# USB_Serial.net
KiCad netlist of a schematic drawn in Altium Designer
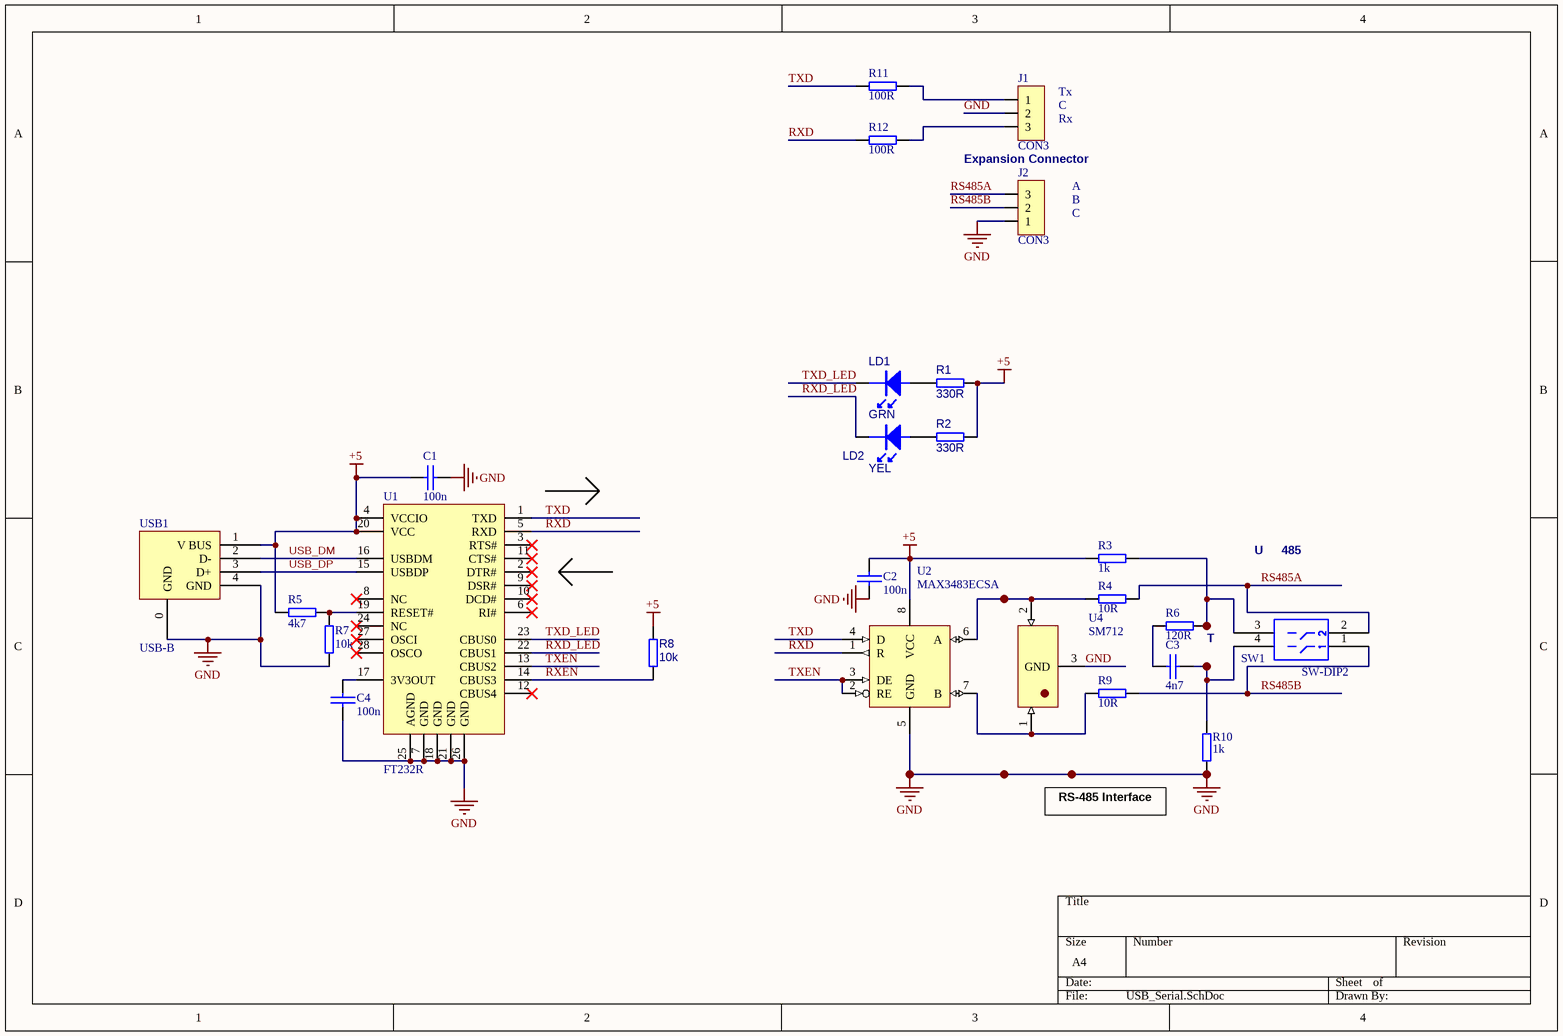
[diagram p0: USB_Serial.SchDoc]

(export (version "E")
  (design (tool "Eeschema 10.0.6"))
  (components
    (comp (ref "C1") (value "100n") (footprint "0603") (libsource (lib "*") (part "CAP")))
    (comp (ref "C2") (value "100n") (footprint "0603") (libsource (lib "*") (part "CAP")))
    (comp (ref "C3") (value "4n7") (footprint "0603") (libsource (lib "*") (part "CAP")))
    (comp (ref "C4") (value "100n") (footprint "0603") (libsource (lib "*") (part "CAP")))
    (comp (ref "J1") (value "CON3") (footprint "TERMS5mm3") (libsource (lib "") (part "CON3_1")))
    (comp (ref "J2") (value "CON3") (footprint "TERMS5mm3") (libsource (lib "DEVICE") (part "CON3")))
    (comp (ref "LD1") (value "GRN") (footprint "0805DIODE") (libsource (lib "*") (part "LED")))
    (comp (ref "LD2") (value "YEL") (footprint "0805DIODE") (libsource (lib "*") (part "LED")))
    (comp (ref "R1") (value "330R") (footprint "0603") (libsource (lib "DEVICE") (part "RES8")))
    (comp (ref "R2") (value "330R") (footprint "0603") (libsource (lib "DEVICE") (part "RES8")))
    (comp (ref "R3") (value "1k") (footprint "0603") (libsource (lib "*") (part "RES8")))
    (comp (ref "R4") (value "10R") (footprint "0603") (libsource (lib "*") (part "RES8")))
    (comp (ref "R5") (value "4k7") (footprint "0603") (libsource (lib "DEVICE") (part "RES8")))
    (comp (ref "R6") (value "120R") (footprint "0603") (libsource (lib "*") (part "RES8")))
    (comp (ref "R7") (value "10k") (footprint "0603") (libsource (lib "DEVICE") (part "RES8")))
    (comp (ref "R8") (value "10k") (footprint "0603") (libsource (lib "DEVICE") (part "RES8")))
    (comp (ref "R9") (value "10R") (footprint "0603") (libsource (lib "*") (part "RES8")))
    (comp (ref "R10") (value "1k") (footprint "0603") (libsource (lib "*") (part "RES8")))
    (comp (ref "R11") (value "100R") (footprint "0603") (libsource (lib "*") (part "RES8")))
    (comp (ref "R12") (value "100R") (footprint "0603") (libsource (lib "*") (part "RES8")))
    (comp (ref "SW1") (value "SW-DIP2") (footprint "DIP4") (libsource (lib "*") (part "SW-DIP2")))
    (comp (ref "U1")
      (value "FT232R")
      (footprint "SSOP28W-handsolder")
      (libsource (lib "FTDI") (part "FT232R"))
    )
    (comp (ref "U2")
      (value "MAX3483ECSA")
      (footprint "so-8")
      (description "RS485 Transceiver")
      (libsource (lib "*") (part "MAX487"))
    )
    (comp (ref "U4")
      (value "SM712")
      (footprint "sot-23")
      (description "RS485 Transorb")
      (fields (field (name "PARTNO.") "2059024"))
      (libsource (lib "TomsSchLib") (part "SM712"))
    )
    (comp (ref "USB1") (value "USB-B") (footprint "USB_MINI_B") (libsource (lib "DEVICE") (part "USB-B")))
  )
  (nets
    (net (code "1") (name "+5") (class "Default")
      (node (ref "C1") (pin "2") (pintype "passive"))
      (node (ref "C2") (pin "1") (pintype "passive"))
      (node (ref "R1") (pin "1") (pintype "passive"))
      (node (ref "R2") (pin "1") (pintype "passive"))
      (node (ref "R3") (pin "1") (pintype "passive"))
      (node (ref "R5") (pin "1") (pintype "passive"))
      (node (ref "R8") (pin "1") (pintype "passive"))
      (node (ref "U1") (pin "20") (pinfunction "VCC_20") (pintype "passive"))
      (node (ref "U1") (pin "4") (pinfunction "VCCIO_4") (pintype "passive"))
      (node (ref "U2") (pin "8") (pinfunction "VCC_8") (pintype "power_in"))
      (node (ref "USB1") (pin "1") (pinfunction "V_BUS_1") (pintype "passive"))
    )
    (net (code "2") (name "/RS485A") (class "Default")
      (node (ref "J2") (pin "3") (pinfunction "3_3") (pintype "passive"))
      (node (ref "R4") (pin "2") (pintype "passive"))
      (node (ref "SW1") (pin "2") (pintype "passive"))
    )
    (net (code "3") (name "/RS485B") (class "Default")
      (node (ref "J2") (pin "2") (pinfunction "2_2") (pintype "passive"))
      (node (ref "R9") (pin "2") (pintype "passive"))
      (node (ref "SW1") (pin "1") (pintype "passive"))
    )
    (net (code "4") (name "/RXD") (class "Default")
      (node (ref "R12") (pin "1") (pintype "passive"))
      (node (ref "U1") (pin "5") (pinfunction "RXD_5") (pintype "passive"))
      (node (ref "U2") (pin "1") (pinfunction "R_1") (pintype "output"))
    )
    (net (code "5") (name "/RXD_LED") (class "Default")
      (node (ref "LD2") (pin "K") (pintype "passive"))
      (node (ref "U1") (pin "22") (pinfunction "CBUS1_22") (pintype "passive"))
    )
    (net (code "6") (name "/RXEN") (class "Default")
      (node (ref "R8") (pin "2") (pintype "passive"))
      (node (ref "U1") (pin "14") (pinfunction "CBUS3_14") (pintype "passive"))
    )
    (net (code "7") (name "/TXD") (class "Default")
      (node (ref "R11") (pin "1") (pintype "passive"))
      (node (ref "U1") (pin "1") (pinfunction "TXD_1") (pintype "passive"))
      (node (ref "U2") (pin "4") (pinfunction "D_4") (pintype "input"))
    )
    (net (code "8") (name "/TXD_LED") (class "Default")
      (node (ref "LD1") (pin "K") (pintype "passive"))
      (node (ref "U1") (pin "23") (pinfunction "CBUS0_23") (pintype "passive"))
    )
    (net (code "9") (name "/TXEN") (class "Default")
      (node (ref "U1") (pin "13") (pinfunction "CBUS2_13") (pintype "passive"))
      (node (ref "U2") (pin "2") (pinfunction "RE_2") (pintype "input"))
      (node (ref "U2") (pin "3") (pinfunction "DE_3") (pintype "input"))
    )
    (net (code "10") (name "/USB_DM") (class "Default")
      (node (ref "U1") (pin "16") (pinfunction "USBDM_16") (pintype "passive"))
      (node (ref "USB1") (pin "2") (pinfunction "D-_2") (pintype "passive"))
    )
    (net (code "11") (name "/USB_DP") (class "Default")
      (node (ref "U1") (pin "15") (pinfunction "USBDP_15") (pintype "passive"))
      (node (ref "USB1") (pin "3") (pinfunction "D+_3") (pintype "passive"))
    )
    (net (code "12") (name "GND") (class "Default")
      (node (ref "C1") (pin "1") (pintype "passive"))
      (node (ref "C2") (pin "2") (pintype "passive"))
      (node (ref "C4") (pin "1") (pintype "passive"))
      (node (ref "J1") (pin "2") (pinfunction "2_2") (pintype "passive"))
      (node (ref "J2") (pin "1") (pinfunction "1_1") (pintype "passive"))
      (node (ref "R10") (pin "2") (pintype "passive"))
      (node (ref "R7") (pin "1") (pintype "passive"))
      (node (ref "U1") (pin "18") (pinfunction "GND_18") (pintype "passive"))
      (node (ref "U1") (pin "21") (pinfunction "GND_21") (pintype "passive"))
      (node (ref "U1") (pin "25") (pinfunction "AGND_25") (pintype "passive"))
      (node (ref "U1") (pin "26") (pinfunction "GND_26") (pintype "passive"))
      (node (ref "U1") (pin "7") (pinfunction "GND_7") (pintype "passive"))
      (node (ref "U2") (pin "5") (pinfunction "GND_5") (pintype "power_in"))
      (node (ref "U4") (pin "3") (pinfunction "GND_3") (pintype "power_in"))
      (node (ref "USB1") (pin "0") (pinfunction "GND_0") (pintype "power_in"))
      (node (ref "USB1") (pin "4") (pinfunction "GND_4") (pintype "passive"))
    )
    (net (code "13") (name "Net-(C3-Pad1)") (class "Default")
      (node (ref "C3") (pin "1") (pintype "passive"))
      (node (ref "R6") (pin "1") (pintype "passive"))
    )
    (net (code "14") (name "Net-(C3-Pad2)") (class "Default")
      (node (ref "C3") (pin "2") (pintype "passive"))
      (node (ref "R10") (pin "1") (pintype "passive"))
      (node (ref "SW1") (pin "4") (pintype "passive"))
    )
    (net (code "15") (name "Net-(J1-Pad1)") (class "Default")
      (node (ref "J1") (pin "1") (pinfunction "1_1") (pintype "passive"))
      (node (ref "R11") (pin "2") (pintype "passive"))
    )
    (net (code "16") (name "Net-(J1-Pad3)") (class "Default")
      (node (ref "J1") (pin "3") (pinfunction "3_3") (pintype "passive"))
      (node (ref "R12") (pin "2") (pintype "passive"))
    )
    (net (code "17") (name "Net-(LD1-PadA)") (class "Default")
      (node (ref "LD1") (pin "A") (pintype "passive"))
      (node (ref "R1") (pin "2") (pintype "passive"))
    )
    (net (code "18") (name "Net-(LD2-PadA)") (class "Default")
      (node (ref "LD2") (pin "A") (pintype "passive"))
      (node (ref "R2") (pin "2") (pintype "passive"))
    )
    (net (code "19") (name "Net-(R3-Pad2)") (class "Default")
      (node (ref "R3") (pin "2") (pintype "passive"))
      (node (ref "R6") (pin "2") (pintype "passive"))
      (node (ref "SW1") (pin "3") (pintype "passive"))
    )
    (net (code "20") (name "Net-(U1-3V3OUT)") (class "Default")
      (node (ref "C4") (pin "2") (pintype "passive"))
      (node (ref "U1") (pin "17") (pinfunction "3V3OUT_17") (pintype "passive"))
    )
    (net (code "21") (name "Net-(U1-RESET#)") (class "Default")
      (node (ref "R5") (pin "2") (pintype "passive"))
      (node (ref "R7") (pin "2") (pintype "passive"))
      (node (ref "U1") (pin "19") (pinfunction "RESET#_19") (pintype "passive"))
    )
    (net (code "22") (name "Net-(U2-A)") (class "Default")
      (node (ref "R4") (pin "1") (pintype "passive"))
      (node (ref "U2") (pin "6") (pinfunction "A_6") (pintype "bidirectional"))
      (node (ref "U4") (pin "2") (pintype "input"))
    )
    (net (code "23") (name "Net-(U2-B)") (class "Default")
      (node (ref "R9") (pin "1") (pintype "passive"))
      (node (ref "U2") (pin "7") (pinfunction "B_7") (pintype "bidirectional"))
      (node (ref "U4") (pin "1") (pintype "input"))
    )
    (net (code "24") (name "unconnected-(U1-CBUS4-Pad12)") (class "Default")
      (node (ref "U1") (pin "12") (pinfunction "CBUS4_12") (pintype "passive+no_connect"))
    )
    (net (code "25") (name "unconnected-(U1-CTS#-Pad11)") (class "Default")
      (node (ref "U1") (pin "11") (pinfunction "CTS#_11") (pintype "passive+no_connect"))
    )
    (net (code "26") (name "unconnected-(U1-DCD#-Pad10)") (class "Default")
      (node (ref "U1") (pin "10") (pinfunction "DCD#_10") (pintype "passive+no_connect"))
    )
    (net (code "27") (name "unconnected-(U1-DSR#-Pad9)") (class "Default")
      (node (ref "U1") (pin "9") (pinfunction "DSR#_9") (pintype "passive+no_connect"))
    )
    (net (code "28") (name "unconnected-(U1-DTR#-Pad2)") (class "Default")
      (node (ref "U1") (pin "2") (pinfunction "DTR#_2") (pintype "passive+no_connect"))
    )
    (net (code "29") (name "unconnected-(U1-NC-Pad8)") (class "Default")
      (node (ref "U1") (pin "8") (pinfunction "NC_8") (pintype "passive+no_connect"))
    )
    (net (code "30") (name "unconnected-(U1-NC-Pad24)") (class "Default")
      (node (ref "U1") (pin "24") (pinfunction "NC_24") (pintype "passive+no_connect"))
    )
    (net (code "31") (name "unconnected-(U1-OSCI-Pad27)") (class "Default")
      (node (ref "U1") (pin "27") (pinfunction "OSCI_27") (pintype "passive+no_connect"))
    )
    (net (code "32") (name "unconnected-(U1-OSCO-Pad28)") (class "Default")
      (node (ref "U1") (pin "28") (pinfunction "OSCO_28") (pintype "passive+no_connect"))
    )
    (net (code "33") (name "unconnected-(U1-RI#-Pad6)") (class "Default")
      (node (ref "U1") (pin "6") (pinfunction "RI#_6") (pintype "passive+no_connect"))
    )
    (net (code "34") (name "unconnected-(U1-RTS#-Pad3)") (class "Default")
      (node (ref "U1") (pin "3") (pinfunction "RTS#_3") (pintype "passive+no_connect"))
    )
  )
)
